# board_A4988.net
KiCad netlist of a schematic drawn in EAGLE
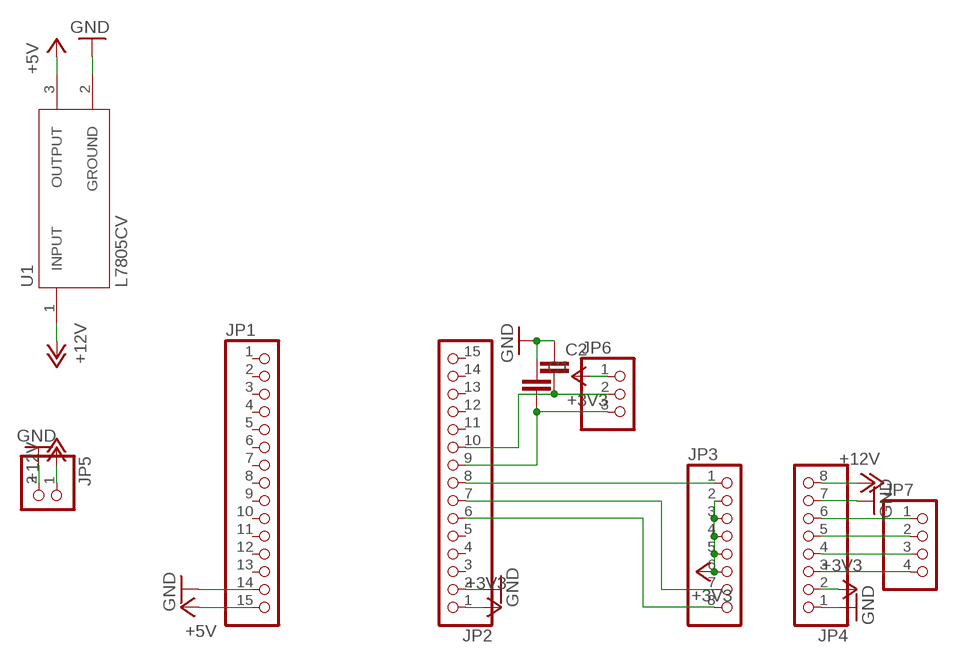
[diagram p0: schematic, sheet 1]

(export (version "E")
  (design (tool "Eeschema 10.0.6"))
  (components
    (comp (ref "C1")
      (value "C-EU025-030X050")
      (footprint "eagle-import:C025-030X050")
      (libsource (lib "eagle-import") (part "C-EU025-030X050"))
    )
    (comp (ref "C2")
      (value "C-EU025-030X050")
      (footprint "eagle-import:C025-030X050")
      (libsource (lib "eagle-import") (part "C-EU025-030X050"))
    )
    (comp (ref "JP1")
      (value "PINHD-1X15")
      (footprint "eagle-import:1X15")
      (libsource (lib "eagle-import") (part "PINHD-1X15"))
    )
    (comp (ref "JP2")
      (value "PINHD-1X15")
      (footprint "eagle-import:1X15")
      (libsource (lib "eagle-import") (part "PINHD-1X15"))
    )
    (comp (ref "JP3")
      (value "PINHD-1X8")
      (footprint "eagle-import:1X08")
      (libsource (lib "eagle-import") (part "PINHD-1X8"))
    )
    (comp (ref "JP4")
      (value "PINHD-1X8")
      (footprint "eagle-import:1X08")
      (libsource (lib "eagle-import") (part "PINHD-1X8"))
    )
    (comp (ref "JP5")
      (value "PINHD-1X2")
      (footprint "eagle-import:1X02")
      (libsource (lib "eagle-import") (part "PINHD-1X2"))
    )
    (comp (ref "JP6")
      (value "PINHD-1X3")
      (footprint "eagle-import:1X03")
      (libsource (lib "eagle-import") (part "PINHD-1X3"))
    )
    (comp (ref "JP7")
      (value "PINHD-1X4")
      (footprint "eagle-import:1X04")
      (libsource (lib "eagle-import") (part "PINHD-1X4"))
    )
    (comp (ref "U1")
      (value "L7805CV")
      (footprint "eagle-import:TO255P1040X460X1968-3")
      (fields (field (name "MF") "STMicroelectronics"))
      (libsource (lib "eagle-import") (part "L7805CV"))
    )
  )
  (nets
    (net (code "1") (name "+3V3") (class "Default")
      (node (ref "JP2") (pin "1") (pinfunction "1_1") (pintype "passive"))
      (node (ref "JP3") (pin "2") (pinfunction "2_2") (pintype "passive"))
      (node (ref "JP3") (pin "3") (pinfunction "3_3") (pintype "passive"))
      (node (ref "JP3") (pin "4") (pinfunction "4_4") (pintype "passive"))
      (node (ref "JP3") (pin "5") (pinfunction "5_5") (pintype "passive"))
      (node (ref "JP3") (pin "6") (pinfunction "6_6") (pintype "passive"))
      (node (ref "JP4") (pin "2") (pinfunction "2_2") (pintype "passive"))
      (node (ref "JP6") (pin "1") (pinfunction "1_1") (pintype "passive"))
    )
    (net (code "2") (name "+5V") (class "Default")
      (node (ref "JP1") (pin "15") (pinfunction "15_15") (pintype "passive"))
      (node (ref "U1") (pin "3") (pinfunction "OUTPUT_3") (pintype "output"))
    )
    (net (code "3") (name "+12V") (class "Default")
      (node (ref "JP4") (pin "8") (pinfunction "8_8") (pintype "passive"))
      (node (ref "JP5") (pin "1") (pinfunction "1_1") (pintype "passive"))
      (node (ref "U1") (pin "1") (pinfunction "INPUT_1") (pintype "input"))
    )
    (net (code "4") (name "GND") (class "Default")
      (node (ref "C1") (pin "1") (pinfunction "1_1") (pintype "passive"))
      (node (ref "C2") (pin "1") (pinfunction "1_1") (pintype "passive"))
      (node (ref "JP1") (pin "14") (pinfunction "14_14") (pintype "passive"))
      (node (ref "JP2") (pin "2") (pinfunction "2_2") (pintype "passive"))
      (node (ref "JP4") (pin "1") (pinfunction "1_1") (pintype "passive"))
      (node (ref "JP4") (pin "7") (pinfunction "7_7") (pintype "passive"))
      (node (ref "JP5") (pin "2") (pinfunction "2_2") (pintype "passive"))
      (node (ref "U1") (pin "2") (pinfunction "GROUND_2") (pintype "power_in"))
    )
    (net (code "5") (name "Net-(C1-Pad2)") (class "Default")
      (node (ref "C1") (pin "2") (pinfunction "2_2") (pintype "passive"))
      (node (ref "JP2") (pin "9") (pinfunction "9_9") (pintype "passive"))
      (node (ref "JP6") (pin "3") (pinfunction "3_3") (pintype "passive"))
    )
    (net (code "6") (name "Net-(C2-Pad2)") (class "Default")
      (node (ref "C2") (pin "2") (pinfunction "2_2") (pintype "passive"))
      (node (ref "JP2") (pin "10") (pinfunction "10_10") (pintype "passive"))
      (node (ref "JP6") (pin "2") (pinfunction "2_2") (pintype "passive"))
    )
    (net (code "7") (name "Net-(JP2-Pad6)") (class "Default")
      (node (ref "JP2") (pin "6") (pinfunction "6_6") (pintype "passive"))
      (node (ref "JP3") (pin "8") (pinfunction "8_8") (pintype "passive"))
    )
    (net (code "8") (name "Net-(JP2-Pad7)") (class "Default")
      (node (ref "JP2") (pin "7") (pinfunction "7_7") (pintype "passive"))
      (node (ref "JP3") (pin "7") (pinfunction "7_7") (pintype "passive"))
    )
    (net (code "9") (name "Net-(JP2-Pad8)") (class "Default")
      (node (ref "JP2") (pin "8") (pinfunction "8_8") (pintype "passive"))
      (node (ref "JP3") (pin "1") (pinfunction "1_1") (pintype "passive"))
    )
    (net (code "10") (name "Net-(JP4-Pad3)") (class "Default")
      (node (ref "JP4") (pin "3") (pinfunction "3_3") (pintype "passive"))
      (node (ref "JP7") (pin "4") (pinfunction "4_4") (pintype "passive"))
    )
    (net (code "11") (name "Net-(JP4-Pad4)") (class "Default")
      (node (ref "JP4") (pin "4") (pinfunction "4_4") (pintype "passive"))
      (node (ref "JP7") (pin "3") (pinfunction "3_3") (pintype "passive"))
    )
    (net (code "12") (name "Net-(JP4-Pad5)") (class "Default")
      (node (ref "JP4") (pin "5") (pinfunction "5_5") (pintype "passive"))
      (node (ref "JP7") (pin "2") (pinfunction "2_2") (pintype "passive"))
    )
    (net (code "13") (name "Net-(JP4-Pad6)") (class "Default")
      (node (ref "JP4") (pin "6") (pinfunction "6_6") (pintype "passive"))
      (node (ref "JP7") (pin "1") (pinfunction "1_1") (pintype "passive"))
    )
    (net (code "14") (name "unconnected-(JP1-Pad1)") (class "Default")
      (node (ref "JP1") (pin "1") (pinfunction "1_1") (pintype "passive"))
    )
    (net (code "15") (name "unconnected-(JP1-Pad2)") (class "Default")
      (node (ref "JP1") (pin "2") (pinfunction "2_2") (pintype "passive"))
    )
    (net (code "16") (name "unconnected-(JP1-Pad3)") (class "Default")
      (node (ref "JP1") (pin "3") (pinfunction "3_3") (pintype "passive"))
    )
    (net (code "17") (name "unconnected-(JP1-Pad4)") (class "Default")
      (node (ref "JP1") (pin "4") (pinfunction "4_4") (pintype "passive"))
    )
    (net (code "18") (name "unconnected-(JP1-Pad5)") (class "Default")
      (node (ref "JP1") (pin "5") (pinfunction "5_5") (pintype "passive"))
    )
    (net (code "19") (name "unconnected-(JP1-Pad6)") (class "Default")
      (node (ref "JP1") (pin "6") (pinfunction "6_6") (pintype "passive"))
    )
    (net (code "20") (name "unconnected-(JP1-Pad7)") (class "Default")
      (node (ref "JP1") (pin "7") (pinfunction "7_7") (pintype "passive"))
    )
    (net (code "21") (name "unconnected-(JP1-Pad8)") (class "Default")
      (node (ref "JP1") (pin "8") (pinfunction "8_8") (pintype "passive"))
    )
    (net (code "22") (name "unconnected-(JP1-Pad9)") (class "Default")
      (node (ref "JP1") (pin "9") (pinfunction "9_9") (pintype "passive"))
    )
    (net (code "23") (name "unconnected-(JP1-Pad10)") (class "Default")
      (node (ref "JP1") (pin "10") (pinfunction "10_10") (pintype "passive"))
    )
    (net (code "24") (name "unconnected-(JP1-Pad11)") (class "Default")
      (node (ref "JP1") (pin "11") (pinfunction "11_11") (pintype "passive"))
    )
    (net (code "25") (name "unconnected-(JP1-Pad12)") (class "Default")
      (node (ref "JP1") (pin "12") (pinfunction "12_12") (pintype "passive"))
    )
    (net (code "26") (name "unconnected-(JP1-Pad13)") (class "Default")
      (node (ref "JP1") (pin "13") (pinfunction "13_13") (pintype "passive"))
    )
    (net (code "27") (name "unconnected-(JP2-Pad3)") (class "Default")
      (node (ref "JP2") (pin "3") (pinfunction "3_3") (pintype "passive"))
    )
    (net (code "28") (name "unconnected-(JP2-Pad4)") (class "Default")
      (node (ref "JP2") (pin "4") (pinfunction "4_4") (pintype "passive"))
    )
    (net (code "29") (name "unconnected-(JP2-Pad5)") (class "Default")
      (node (ref "JP2") (pin "5") (pinfunction "5_5") (pintype "passive"))
    )
    (net (code "30") (name "unconnected-(JP2-Pad11)") (class "Default")
      (node (ref "JP2") (pin "11") (pinfunction "11_11") (pintype "passive"))
    )
    (net (code "31") (name "unconnected-(JP2-Pad12)") (class "Default")
      (node (ref "JP2") (pin "12") (pinfunction "12_12") (pintype "passive"))
    )
    (net (code "32") (name "unconnected-(JP2-Pad13)") (class "Default")
      (node (ref "JP2") (pin "13") (pinfunction "13_13") (pintype "passive"))
    )
    (net (code "33") (name "unconnected-(JP2-Pad14)") (class "Default")
      (node (ref "JP2") (pin "14") (pinfunction "14_14") (pintype "passive"))
    )
    (net (code "34") (name "unconnected-(JP2-Pad15)") (class "Default")
      (node (ref "JP2") (pin "15") (pinfunction "15_15") (pintype "passive"))
    )
  )
)
